# AD9833_FG_Out.net
KiCad netlist of a schematic drawn in EAGLE
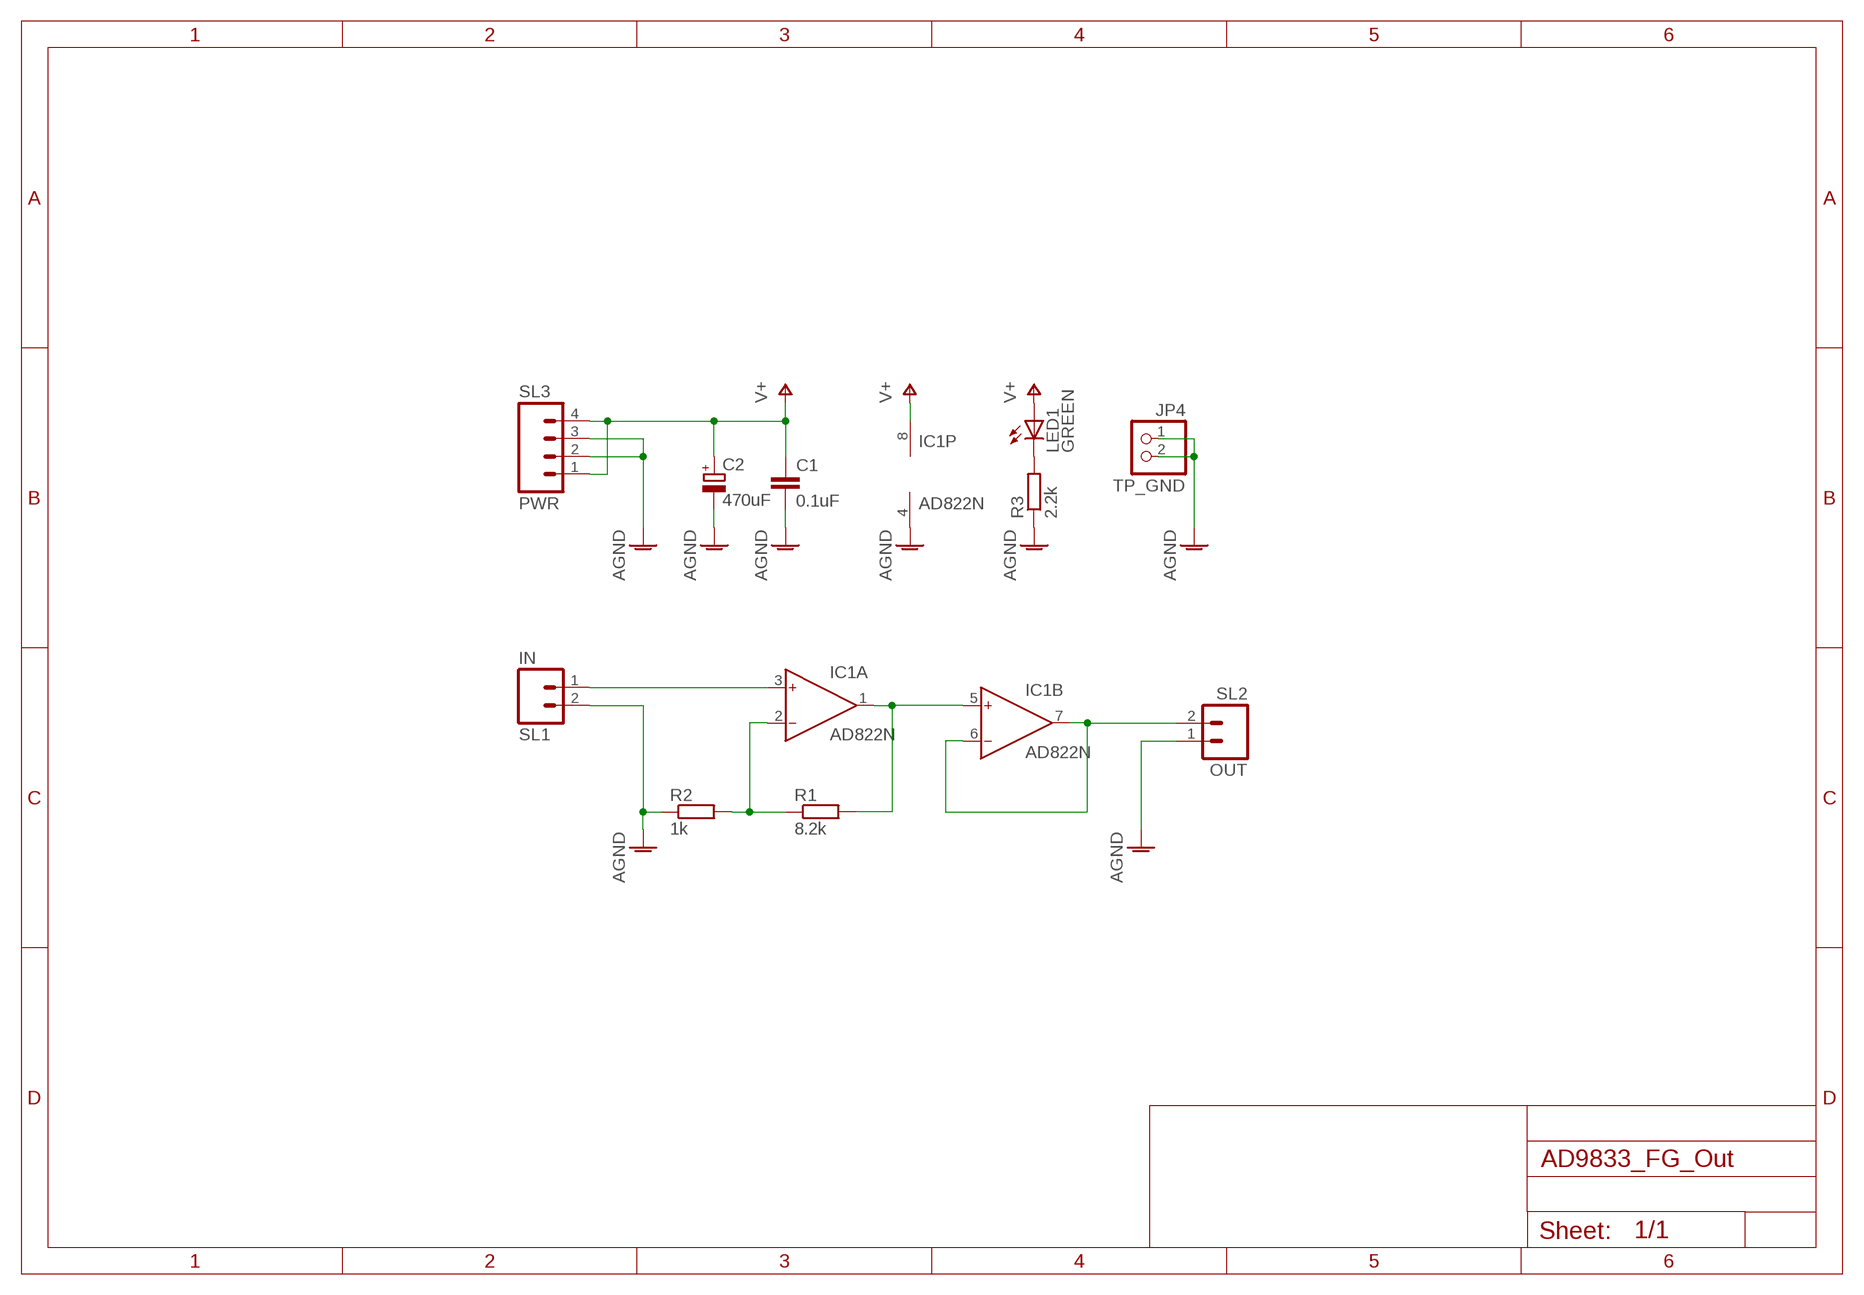
[diagram p0: schematic, sheet 1]

(export (version "E")
  (design (tool "Eeschema 10.0.6"))
  (components
    (comp (ref "C1")
      (value "0.1uF")
      (footprint "eagle-import:C025-024X044")
      (libsource (lib "eagle-import") (part "C-EU025-024X044"))
    )
    (comp (ref "C2")
      (value "470uF")
      (footprint "eagle-import:E2,5-7")
      (libsource (lib "eagle-import") (part "CPOL-EUE2.5-7"))
    )
    (comp (ref "IC1")
      (value "AD822N")
      (footprint "eagle-import:DIL08")
      (libsource (lib "eagle-import") (part "AD822N"))
    )
    (comp (ref "JP4")
      (value "TP_GND")
      (footprint "eagle-import:1X02")
      (libsource (lib "eagle-import") (part "PINHD-1X2"))
    )
    (comp (ref "LED1")
      (value "GREEN")
      (footprint "eagle-import:LED3MM")
      (libsource (lib "eagle-import") (part "LED3MM"))
    )
    (comp (ref "R1")
      (value "8.2k")
      (footprint "eagle-import:0207_7")
      (libsource (lib "eagle-import") (part "R-EU_0207/7"))
    )
    (comp (ref "R2")
      (value "1k")
      (footprint "eagle-import:0207_7")
      (libsource (lib "eagle-import") (part "R-EU_0207/7"))
    )
    (comp (ref "R3")
      (value "2.2k")
      (footprint "eagle-import:0207_7")
      (libsource (lib "eagle-import") (part "R-EU_0207/7"))
    )
    (comp (ref "SL1")
      (value "IN")
      (footprint "eagle-import:02P")
      (libsource (lib "eagle-import") (part "M02"))
    )
    (comp (ref "SL2")
      (value "OUT")
      (footprint "eagle-import:02P")
      (libsource (lib "eagle-import") (part "M02"))
    )
    (comp (ref "SL3")
      (value "PWR")
      (footprint "eagle-import:04P")
      (libsource (lib "eagle-import") (part "M04"))
    )
  )
  (nets
    (net (code "1") (name "AGND") (class "Default")
      (node (ref "C1") (pin "2") (pinfunction "2_2") (pintype "passive"))
      (node (ref "C2") (pin "-") (pinfunction "-_-") (pintype "passive"))
      (node (ref "IC1") (pin "4") (pinfunction "V-_4") (pintype "power_in"))
      (node (ref "JP4") (pin "1") (pinfunction "1_1") (pintype "passive"))
      (node (ref "JP4") (pin "2") (pinfunction "2_2") (pintype "passive"))
      (node (ref "R2") (pin "1") (pinfunction "1_1") (pintype "passive"))
      (node (ref "R3") (pin "1") (pinfunction "1_1") (pintype "passive"))
      (node (ref "SL1") (pin "2") (pinfunction "2_2") (pintype "passive"))
      (node (ref "SL2") (pin "1") (pinfunction "1_1") (pintype "passive"))
      (node (ref "SL3") (pin "2") (pinfunction "2_2") (pintype "passive"))
      (node (ref "SL3") (pin "3") (pinfunction "3_3") (pintype "passive"))
    )
    (net (code "2") (name "Net-(IC1A-IN+)") (class "Default")
      (node (ref "IC1") (pin "3") (pinfunction "IN+_3") (pintype "input"))
      (node (ref "SL1") (pin "1") (pinfunction "1_1") (pintype "passive"))
    )
    (net (code "3") (name "Net-(IC1A-IN-)") (class "Default")
      (node (ref "IC1") (pin "2") (pinfunction "IN-_2") (pintype "input"))
      (node (ref "R1") (pin "1") (pinfunction "1_1") (pintype "passive"))
      (node (ref "R2") (pin "2") (pinfunction "2_2") (pintype "passive"))
    )
    (net (code "4") (name "Net-(IC1A-OUT)") (class "Default")
      (node (ref "IC1") (pin "1") (pinfunction "OUT_1") (pintype "output"))
      (node (ref "IC1") (pin "5") (pinfunction "IN+_5") (pintype "input"))
      (node (ref "R1") (pin "2") (pinfunction "2_2") (pintype "passive"))
    )
    (net (code "5") (name "Net-(IC1B-IN-)") (class "Default")
      (node (ref "IC1") (pin "6") (pinfunction "IN-_6") (pintype "input"))
      (node (ref "IC1") (pin "7") (pinfunction "OUT_7") (pintype "output"))
      (node (ref "SL2") (pin "2") (pinfunction "2_2") (pintype "passive"))
    )
    (net (code "6") (name "Net-(LED1-C)") (class "Default")
      (node (ref "LED1") (pin "K") (pinfunction "C_K") (pintype "passive"))
      (node (ref "R3") (pin "2") (pinfunction "2_2") (pintype "passive"))
    )
    (net (code "7") (name "V+") (class "Default")
      (node (ref "C1") (pin "1") (pinfunction "1_1") (pintype "passive"))
      (node (ref "C2") (pin "+") (pinfunction "+_+") (pintype "passive"))
      (node (ref "IC1") (pin "8") (pinfunction "V+_8") (pintype "power_in"))
      (node (ref "LED1") (pin "A") (pinfunction "A_A") (pintype "passive"))
      (node (ref "SL3") (pin "1") (pinfunction "1_1") (pintype "passive"))
      (node (ref "SL3") (pin "4") (pinfunction "4_4") (pintype "passive"))
    )
  )
)
